# Sheet2.net
KiCad netlist of a schematic drawn in Altium Designer
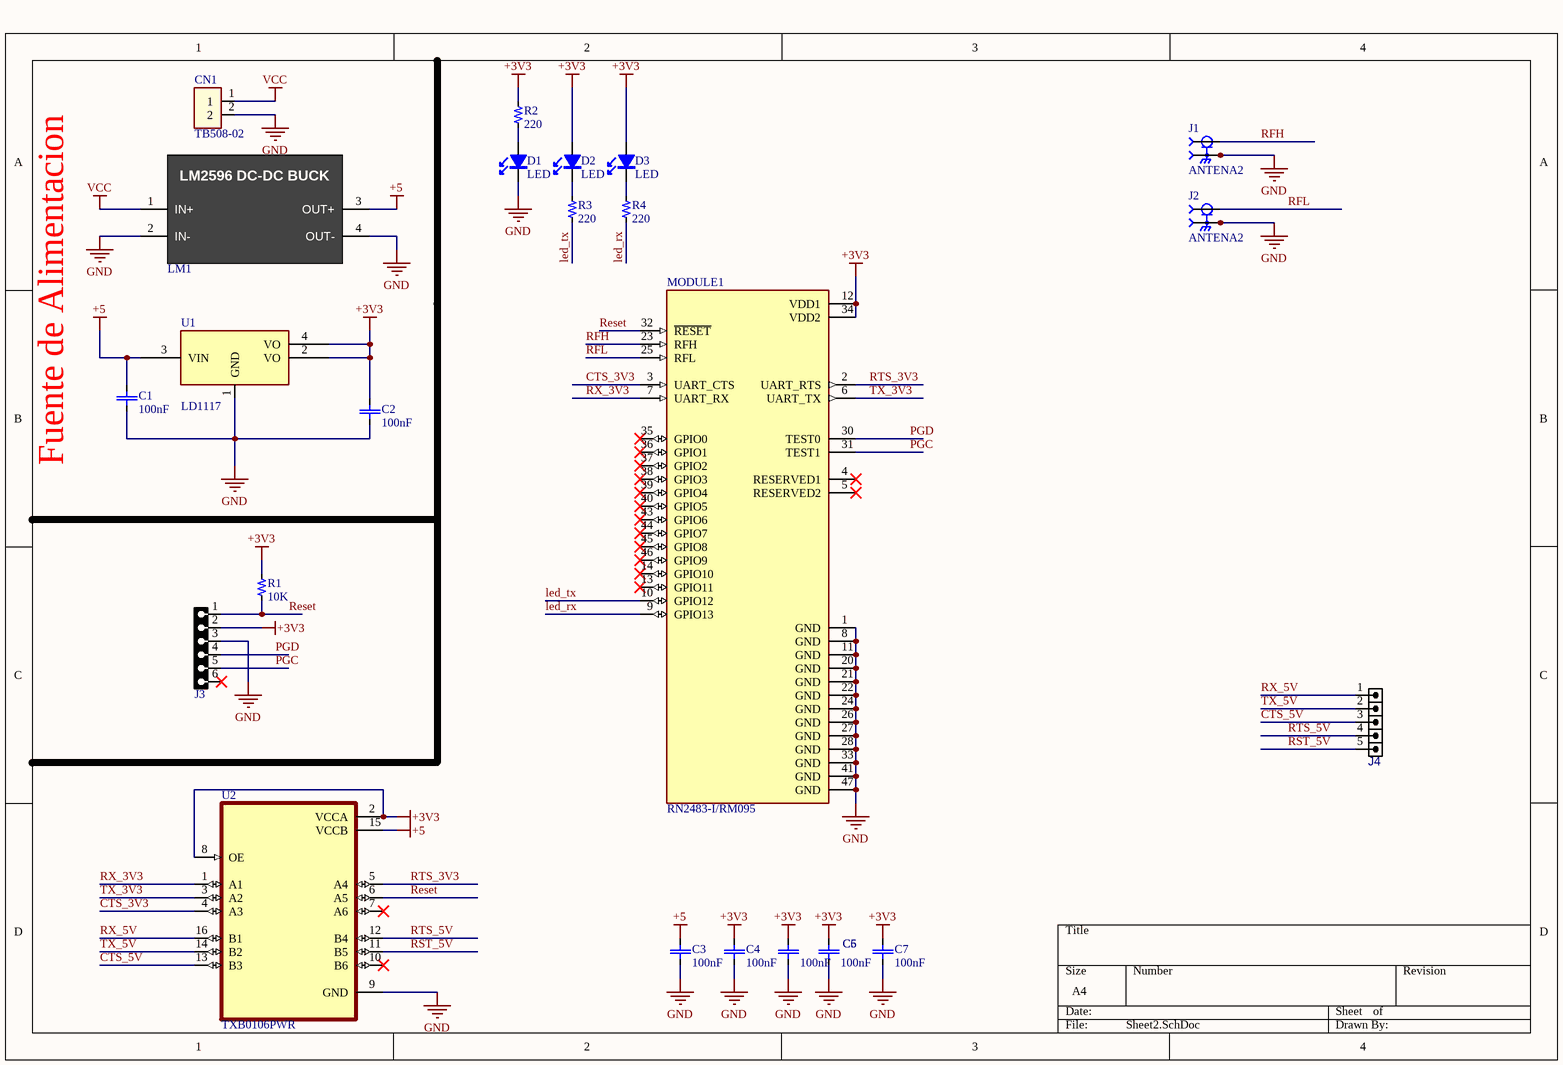
[diagram p0: Sheet2.SchDoc]

(export (version "E")
  (design (tool "Eeschema 10.0.6"))
  (components
    (comp (ref "C1")
      (value "100nF")
      (footprint "C0805")
      (description "Capacitor without polarity")
      (fields (field (name "VOLTAGE") "25V"))
      (libsource (lib "RasUNMSM") (part "Capacitor"))
    )
    (comp (ref "C2")
      (value "100nF")
      (footprint "C0805")
      (description "Capacitor without polarity")
      (fields (field (name "VOLTAGE") "25V"))
      (libsource (lib "RasUNMSM") (part "Capacitor"))
    )
    (comp (ref "C3")
      (value "100nF")
      (footprint "C0805")
      (description "Capacitor without polarity")
      (fields (field (name "VOLTAGE") "25V"))
      (libsource (lib "RasUNMSM") (part "Capacitor"))
    )
    (comp (ref "C4")
      (value "100nF")
      (footprint "C0805")
      (description "Capacitor without polarity")
      (fields (field (name "VOLTAGE") "25V"))
      (libsource (lib "RasUNMSM") (part "Capacitor"))
    )
    (comp (ref "C5")
      (value "100nF")
      (footprint "C0805")
      (description "Capacitor without polarity")
      (fields (field (name "VOLTAGE") "25V"))
      (libsource (lib "RasUNMSM") (part "Capacitor"))
    )
    (comp (ref "C6")
      (value "100nF")
      (footprint "C0805")
      (description "Capacitor without polarity")
      (fields (field (name "VOLTAGE") "25V"))
      (libsource (lib "RasUNMSM") (part "Capacitor"))
    )
    (comp (ref "C7")
      (value "100nF")
      (footprint "C0805")
      (description "Capacitor without polarity")
      (fields (field (name "VOLTAGE") "25V"))
      (libsource (lib "RasUNMSM") (part "Capacitor"))
    )
    (comp (ref "CN1")
      (value "TB508-02")
      (footprint "TB508-02")
      (description "Terminal Block")
      (libsource (lib "RasUNMSM") (part "TB-02"))
    )
    (comp (ref "D1")
      (value "LED")
      (footprint "LED-0805")
      (description "LED - Light-Emitting Diode")
      (libsource (lib "RasUNMSM") (part "LED"))
    )
    (comp (ref "D2")
      (value "LED")
      (footprint "LED-0805")
      (description "LED - Light-Emitting Diode")
      (libsource (lib "RasUNMSM") (part "LED"))
    )
    (comp (ref "D3")
      (value "LED")
      (footprint "LED-0805")
      (description "LED - Light-Emitting Diode")
      (libsource (lib "RasUNMSM") (part "LED"))
    )
    (comp (ref "J1")
      (value "ANTENA2")
      (footprint "SAMTEC_SMA-J-P-X-ST-MT1")
      (description "SMA Connector Jack, Female Socket 50Ohm Surface Mount, Through Hole Solder")
      (fields (field (name "MF") "Samtec") (field (name "MP") "SMA-J-P-H-ST-MT1"))
      (libsource (lib "MIKROBUS_LORA") (part "SMA-J-P-X-ST-MT1"))
    )
    (comp (ref "J2")
      (value "ANTENA2")
      (footprint "SAMTEC_SMA-J-P-X-ST-MT1")
      (description "SMA Connector Jack, Female Socket 50Ohm Surface Mount, Through Hole Solder")
      (fields (field (name "MF") "Samtec") (field (name "MP") "SMA-J-P-H-ST-MT1"))
      (libsource (lib "MIKROBUS_LORA") (part "SMA-J-P-X-ST-MT1"))
    )
    (comp (ref "J3")
      (value "HDRF6")
      (footprint "HDRRS_F_1X6")
      (description "CONN, HEADER, Female, pitch: 2.54mm, 6POS")
      (libsource (lib "Headers") (part "Header Female smd 1x6 horizontal"))
    )
    (comp (ref "J4")
      (value "HDRM5")
      (footprint "HDRS_M_1X5")
      (description "CONN, HEADER, Male, pitch: 2.54mm, 5POS, SMD")
      (fields (field (name "MANF_P#") "PBC36SAAN") (field (name "MANF") "Sullins"))
      (libsource (lib "Headers") (part "Header Male 1x5 smd"))
    )
    (comp (ref "LM1") (value "LM2596?") (footprint "LM2596 - 3D") (libsource (lib "LM2596") (part "LM2596?")))
    (comp (ref "MODULE1")
      (value "RN2483-I/RM095")
      (footprint "MICROCHIP_RN2483-I/RM095")
      (description "Sub-GHz Dual Band Long Range Transceiver LoRa Module")
      (fields (field (name "MF") "Microchip"))
      (libsource (lib "MIKROBUS_LORA") (part "RN2483-I/RM095"))
    )
    (comp (ref "R1")
      (value "10K")
      (footprint "R0805")
      (description "Single resistor")
      (fields (field (name "POWER") "0.125W"))
      (libsource (lib "RasUNMSM") (part "Resistor"))
    )
    (comp (ref "R2")
      (value "220")
      (footprint "R0805")
      (description "Single resistor")
      (fields (field (name "POWER") "0.125W"))
      (libsource (lib "RasUNMSM") (part "Resistor"))
    )
    (comp (ref "R3")
      (value "220")
      (footprint "R0805")
      (description "Single resistor")
      (fields (field (name "POWER") "0.125W"))
      (libsource (lib "RasUNMSM") (part "Resistor"))
    )
    (comp (ref "R4")
      (value "220")
      (footprint "R0805")
      (description "Single resistor")
      (fields (field (name "POWER") "0.125W"))
      (libsource (lib "RasUNMSM") (part "Resistor"))
    )
    (comp (ref "U1")
      (value "LD1117")
      (footprint "SOT223_4")
      (description "REG, Linear, LDO1V, 0.8A, SOT-223")
      (fields
        (field (name "MANF_P#") "LD1117, LM1117, AMS1117, TLV1117, REG1117, NCP1117, LT1117, SPX1117")
        (field (name "MANF") "TI, ON, ST")
      )
      (libsource (lib "Reguladores") (part "VREG_1117_SOT223"))
    )
    (comp (ref "U2")
      (value "TXB0106PWR")
      (footprint "SOP65P640X120-16N")
      (fields (field (name "MF") "Texas Instruments"))
      (libsource (lib "MIKROBUS_LORA") (part "TXB0106PWR"))
    )
  )
  (nets
    (net (code "1") (name "+3V3") (class "Default")
      (node (ref "C2") (pin "2") (pinfunction "2_2") (pintype "passive"))
      (node (ref "C4") (pin "2") (pinfunction "2_2") (pintype "passive"))
      (node (ref "C5") (pin "2") (pinfunction "2_2") (pintype "passive"))
      (node (ref "C6") (pin "2") (pinfunction "2_2") (pintype "passive"))
      (node (ref "C7") (pin "2") (pinfunction "2_2") (pintype "passive"))
      (node (ref "D2") (pin "2") (pinfunction "2_2") (pintype "passive"))
      (node (ref "D3") (pin "2") (pinfunction "2_2") (pintype "passive"))
      (node (ref "J3") (pin "2") (pinfunction "2_2") (pintype "passive"))
      (node (ref "MODULE1") (pin "12") (pinfunction "VDD1_12") (pintype "power_in"))
      (node (ref "MODULE1") (pin "34") (pinfunction "VDD2_34") (pintype "power_in"))
      (node (ref "R1") (pin "2") (pinfunction "2_2") (pintype "passive"))
      (node (ref "R2") (pin "2") (pinfunction "2_2") (pintype "passive"))
      (node (ref "U1") (pin "2") (pinfunction "VO_2") (pintype "passive"))
      (node (ref "U1") (pin "4") (pinfunction "VO_4") (pintype "passive"))
      (node (ref "U2") (pin "2") (pinfunction "VCCA_2") (pintype "power_in"))
      (node (ref "U2") (pin "8") (pinfunction "OE_8") (pintype "input"))
    )
    (net (code "2") (name "+5") (class "Default")
      (node (ref "C1") (pin "2") (pinfunction "2_2") (pintype "passive"))
      (node (ref "C3") (pin "2") (pinfunction "2_2") (pintype "passive"))
      (node (ref "LM1") (pin "3") (pinfunction "OUT+_3") (pintype "passive"))
      (node (ref "U1") (pin "3") (pinfunction "VIN_3") (pintype "passive"))
      (node (ref "U2") (pin "15") (pinfunction "VCCB_15") (pintype "power_in"))
    )
    (net (code "3") (name "/CTS_3V3") (class "Default")
      (node (ref "MODULE1") (pin "3") (pinfunction "UART_CTS_3") (pintype "input"))
      (node (ref "U2") (pin "4") (pinfunction "A3_4") (pintype "bidirectional"))
    )
    (net (code "4") (name "/CTS_5V") (class "Default")
      (node (ref "J4") (pin "3") (pinfunction "3_3") (pintype "passive"))
      (node (ref "U2") (pin "13") (pinfunction "B3_13") (pintype "bidirectional"))
    )
    (net (code "5") (name "/PGC") (class "Default")
      (node (ref "J3") (pin "5") (pinfunction "5_5") (pintype "passive"))
      (node (ref "MODULE1") (pin "31") (pinfunction "TEST1_31") (pintype "passive"))
    )
    (net (code "6") (name "/PGD") (class "Default")
      (node (ref "J3") (pin "4") (pinfunction "4_4") (pintype "passive"))
      (node (ref "MODULE1") (pin "30") (pinfunction "TEST0_30") (pintype "passive"))
    )
    (net (code "7") (name "/RFH") (class "Default")
      (node (ref "J1") (pin "1") (pinfunction "1_1") (pintype "passive"))
      (node (ref "MODULE1") (pin "23") (pinfunction "RFH_23") (pintype "input"))
    )
    (net (code "8") (name "/RFL") (class "Default")
      (node (ref "J2") (pin "1") (pinfunction "1_1") (pintype "passive"))
      (node (ref "MODULE1") (pin "25") (pinfunction "RFL_25") (pintype "input"))
    )
    (net (code "9") (name "/RST_5V") (class "Default")
      (node (ref "J4") (pin "5") (pinfunction "5_5") (pintype "passive"))
      (node (ref "U2") (pin "11") (pinfunction "B5_11") (pintype "bidirectional"))
    )
    (net (code "10") (name "/RTS_3V3") (class "Default")
      (node (ref "MODULE1") (pin "2") (pinfunction "UART_RTS_2") (pintype "output"))
      (node (ref "U2") (pin "5") (pinfunction "A4_5") (pintype "bidirectional"))
    )
    (net (code "11") (name "/RTS_5V") (class "Default")
      (node (ref "J4") (pin "4") (pinfunction "4_4") (pintype "passive"))
      (node (ref "U2") (pin "12") (pinfunction "B4_12") (pintype "bidirectional"))
    )
    (net (code "12") (name "/RX_3V3") (class "Default")
      (node (ref "MODULE1") (pin "7") (pinfunction "UART_RX_7") (pintype "input"))
      (node (ref "U2") (pin "1") (pinfunction "A1_1") (pintype "bidirectional"))
    )
    (net (code "13") (name "/RX_5V") (class "Default")
      (node (ref "J4") (pin "1") (pinfunction "1_1") (pintype "passive"))
      (node (ref "U2") (pin "16") (pinfunction "B1_16") (pintype "bidirectional"))
    )
    (net (code "14") (name "/Reset") (class "Default")
      (node (ref "J3") (pin "1") (pinfunction "1_1") (pintype "passive"))
      (node (ref "MODULE1") (pin "32") (pinfunction "~{RESET}_32") (pintype "input"))
      (node (ref "R1") (pin "1") (pinfunction "1_1") (pintype "passive"))
      (node (ref "U2") (pin "6") (pinfunction "A5_6") (pintype "bidirectional"))
    )
    (net (code "15") (name "/TX_3V3") (class "Default")
      (node (ref "MODULE1") (pin "6") (pinfunction "UART_TX_6") (pintype "output"))
      (node (ref "U2") (pin "3") (pinfunction "A2_3") (pintype "bidirectional"))
    )
    (net (code "16") (name "/TX_5V") (class "Default")
      (node (ref "J4") (pin "2") (pinfunction "2_2") (pintype "passive"))
      (node (ref "U2") (pin "14") (pinfunction "B2_14") (pintype "bidirectional"))
    )
    (net (code "17") (name "/led_rx") (class "Default")
      (node (ref "MODULE1") (pin "9") (pinfunction "GPIO13_9") (pintype "bidirectional"))
      (node (ref "R4") (pin "1") (pinfunction "1_1") (pintype "passive"))
    )
    (net (code "18") (name "/led_tx") (class "Default")
      (node (ref "MODULE1") (pin "10") (pinfunction "GPIO12_10") (pintype "bidirectional"))
      (node (ref "R3") (pin "1") (pinfunction "1_1") (pintype "passive"))
    )
    (net (code "19") (name "GND") (class "Default")
      (node (ref "C1") (pin "1") (pinfunction "1_1") (pintype "passive"))
      (node (ref "C2") (pin "1") (pinfunction "1_1") (pintype "passive"))
      (node (ref "C3") (pin "1") (pinfunction "1_1") (pintype "passive"))
      (node (ref "C4") (pin "1") (pinfunction "1_1") (pintype "passive"))
      (node (ref "C5") (pin "1") (pinfunction "1_1") (pintype "passive"))
      (node (ref "C6") (pin "1") (pinfunction "1_1") (pintype "passive"))
      (node (ref "C7") (pin "1") (pinfunction "1_1") (pintype "passive"))
      (node (ref "CN1") (pin "2") (pinfunction "2_2") (pintype "passive"))
      (node (ref "D1") (pin "1") (pinfunction "1_1") (pintype "passive"))
      (node (ref "J1") (pin "2") (pinfunction "2_2") (pintype "passive"))
      (node (ref "J1") (pin "3") (pinfunction "2_3") (pintype "passive"))
      (node (ref "J1") (pin "4") (pinfunction "2_4") (pintype "passive"))
      (node (ref "J1") (pin "5") (pinfunction "2_5") (pintype "passive"))
      (node (ref "J2") (pin "2") (pinfunction "2_2") (pintype "passive"))
      (node (ref "J2") (pin "3") (pinfunction "2_3") (pintype "passive"))
      (node (ref "J2") (pin "4") (pinfunction "2_4") (pintype "passive"))
      (node (ref "J2") (pin "5") (pinfunction "2_5") (pintype "passive"))
      (node (ref "J3") (pin "3") (pinfunction "3_3") (pintype "passive"))
      (node (ref "LM1") (pin "2") (pinfunction "IN-_2") (pintype "passive"))
      (node (ref "LM1") (pin "4") (pinfunction "OUT-_4") (pintype "passive"))
      (node (ref "MODULE1") (pin "1") (pinfunction "GND_1") (pintype "passive"))
      (node (ref "MODULE1") (pin "11") (pinfunction "GND_11") (pintype "passive"))
      (node (ref "MODULE1") (pin "20") (pinfunction "GND_20") (pintype "passive"))
      (node (ref "MODULE1") (pin "21") (pinfunction "GND_21") (pintype "passive"))
      (node (ref "MODULE1") (pin "22") (pinfunction "GND_22") (pintype "passive"))
      (node (ref "MODULE1") (pin "24") (pinfunction "GND_24") (pintype "passive"))
      (node (ref "MODULE1") (pin "26") (pinfunction "GND_26") (pintype "passive"))
      (node (ref "MODULE1") (pin "27") (pinfunction "GND_27") (pintype "passive"))
      (node (ref "MODULE1") (pin "28") (pinfunction "GND_28") (pintype "passive"))
      (node (ref "MODULE1") (pin "33") (pinfunction "GND_33") (pintype "passive"))
      (node (ref "MODULE1") (pin "41") (pinfunction "GND_41") (pintype "passive"))
      (node (ref "MODULE1") (pin "47") (pinfunction "GND_47") (pintype "passive"))
      (node (ref "MODULE1") (pin "8") (pinfunction "GND_8") (pintype "passive"))
      (node (ref "U1") (pin "1") (pinfunction "GND_1") (pintype "passive"))
      (node (ref "U2") (pin "9") (pinfunction "GND_9") (pintype "power_in"))
    )
    (net (code "20") (name "Net-(D1-Pad2)") (class "Default")
      (node (ref "D1") (pin "2") (pinfunction "2_2") (pintype "passive"))
      (node (ref "R2") (pin "1") (pinfunction "1_1") (pintype "passive"))
    )
    (net (code "21") (name "Net-(D2-Pad1)") (class "Default")
      (node (ref "D2") (pin "1") (pinfunction "1_1") (pintype "passive"))
      (node (ref "R3") (pin "2") (pinfunction "2_2") (pintype "passive"))
    )
    (net (code "22") (name "Net-(D3-Pad1)") (class "Default")
      (node (ref "D3") (pin "1") (pinfunction "1_1") (pintype "passive"))
      (node (ref "R4") (pin "2") (pinfunction "2_2") (pintype "passive"))
    )
    (net (code "23") (name "VCC") (class "Default")
      (node (ref "CN1") (pin "1") (pinfunction "1_1") (pintype "passive"))
      (node (ref "LM1") (pin "1") (pinfunction "IN+_1") (pintype "passive"))
    )
    (net (code "24") (name "unconnected-(J3-Pad6)") (class "Default")
      (node (ref "J3") (pin "6") (pinfunction "6_6") (pintype "passive+no_connect"))
    )
    (net (code "25") (name "unconnected-(MODULE1-GPIO0-Pad35)") (class "Default")
      (node (ref "MODULE1") (pin "35") (pinfunction "GPIO0_35") (pintype "bidirectional+no_connect"))
    )
    (net (code "26") (name "unconnected-(MODULE1-GPIO1-Pad36)") (class "Default")
      (node (ref "MODULE1") (pin "36") (pinfunction "GPIO1_36") (pintype "bidirectional+no_connect"))
    )
    (net (code "27") (name "unconnected-(MODULE1-GPIO2-Pad37)") (class "Default")
      (node (ref "MODULE1") (pin "37") (pinfunction "GPIO2_37") (pintype "bidirectional+no_connect"))
    )
    (net (code "28") (name "unconnected-(MODULE1-GPIO3-Pad38)") (class "Default")
      (node (ref "MODULE1") (pin "38") (pinfunction "GPIO3_38") (pintype "bidirectional+no_connect"))
    )
    (net (code "29") (name "unconnected-(MODULE1-GPIO4-Pad39)") (class "Default")
      (node (ref "MODULE1") (pin "39") (pinfunction "GPIO4_39") (pintype "bidirectional+no_connect"))
    )
    (net (code "30") (name "unconnected-(MODULE1-GPIO5-Pad40)") (class "Default")
      (node (ref "MODULE1") (pin "40") (pinfunction "GPIO5_40") (pintype "bidirectional+no_connect"))
    )
    (net (code "31") (name "unconnected-(MODULE1-GPIO6-Pad43)") (class "Default")
      (node (ref "MODULE1") (pin "43") (pinfunction "GPIO6_43") (pintype "bidirectional+no_connect"))
    )
    (net (code "32") (name "unconnected-(MODULE1-GPIO7-Pad44)") (class "Default")
      (node (ref "MODULE1") (pin "44") (pinfunction "GPIO7_44") (pintype "bidirectional+no_connect"))
    )
    (net (code "33") (name "unconnected-(MODULE1-GPIO8-Pad45)") (class "Default")
      (node (ref "MODULE1") (pin "45") (pinfunction "GPIO8_45") (pintype "bidirectional+no_connect"))
    )
    (net (code "34") (name "unconnected-(MODULE1-GPIO9-Pad46)") (class "Default")
      (node (ref "MODULE1") (pin "46") (pinfunction "GPIO9_46") (pintype "bidirectional+no_connect"))
    )
    (net (code "35") (name "unconnected-(MODULE1-GPIO10-Pad14)") (class "Default")
      (node (ref "MODULE1") (pin "14") (pinfunction "GPIO10_14") (pintype "bidirectional+no_connect"))
    )
    (net (code "36") (name "unconnected-(MODULE1-GPIO11-Pad13)") (class "Default")
      (node (ref "MODULE1") (pin "13") (pinfunction "GPIO11_13") (pintype "bidirectional+no_connect"))
    )
    (net (code "37") (name "unconnected-(MODULE1-RESERVED1-Pad4)") (class "Default")
      (node (ref "MODULE1") (pin "4") (pinfunction "RESERVED1_4") (pintype "passive+no_connect"))
    )
    (net (code "38") (name "unconnected-(MODULE1-RESERVED2-Pad5)") (class "Default")
      (node (ref "MODULE1") (pin "5") (pinfunction "RESERVED2_5") (pintype "passive+no_connect"))
    )
    (net (code "39") (name "unconnected-(U2-A6-Pad7)") (class "Default")
      (node (ref "U2") (pin "7") (pinfunction "A6_7") (pintype "bidirectional+no_connect"))
    )
    (net (code "40") (name "unconnected-(U2-B6-Pad10)") (class "Default")
      (node (ref "U2") (pin "10") (pinfunction "B6_10") (pintype "bidirectional+no_connect"))
    )
  )
)
